# updown_counter.net
KiCad netlist of a schematic drawn in EAGLE
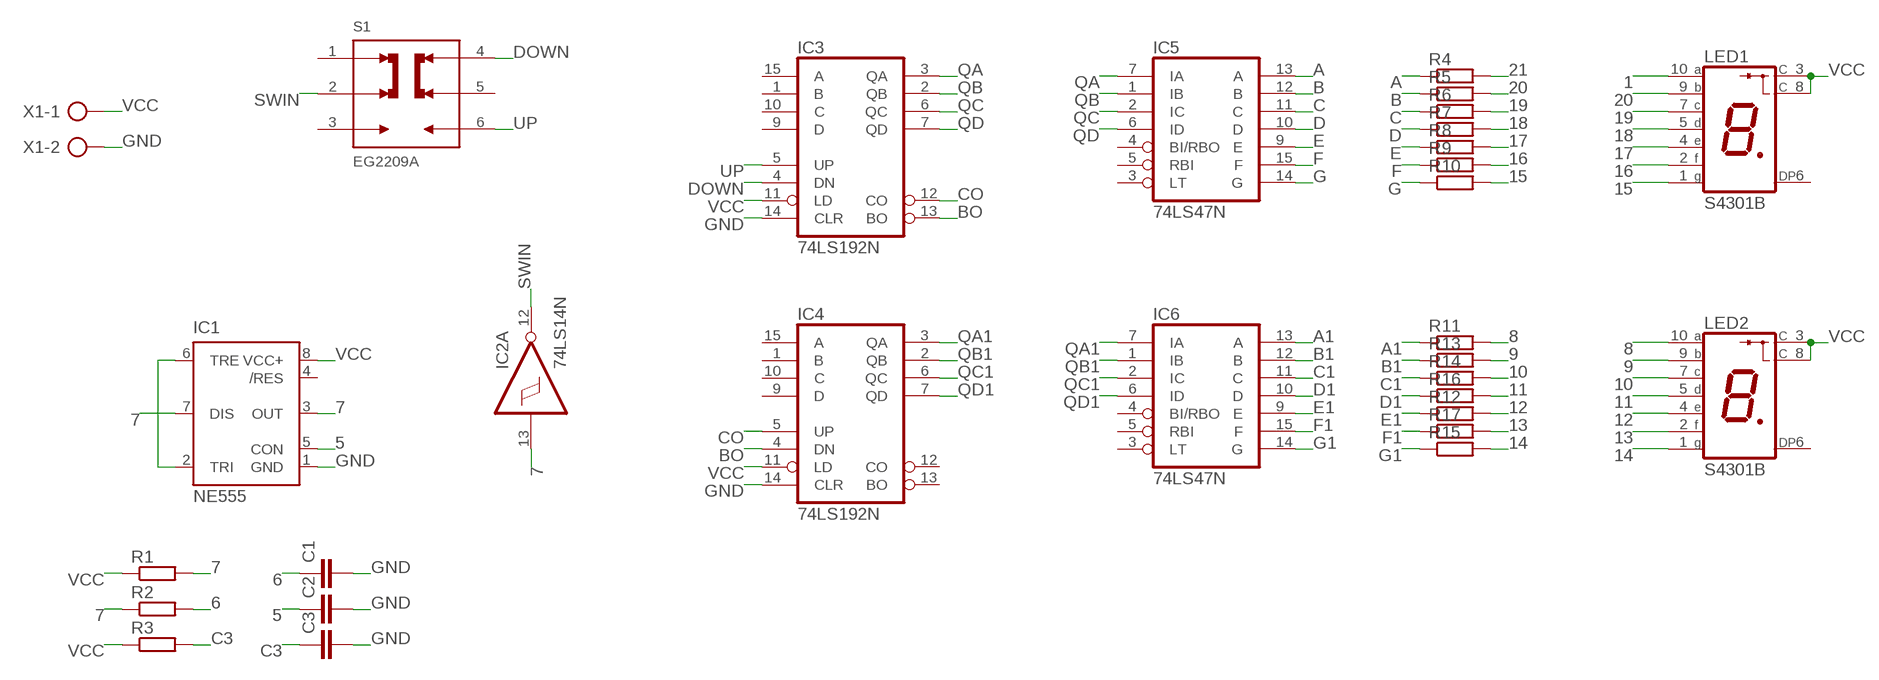
[diagram p0: schematic, sheet 1]

(export (version "E")
  (design (tool "Eeschema 10.0.6"))
  (components
    (comp (ref "C1")
      (value "C-EU025-025X050")
      (footprint "eagle-import:C025-025X050")
      (libsource (lib "eagle-import") (part "C-EU025-025X050"))
    )
    (comp (ref "C2")
      (value "C-EU025-025X050")
      (footprint "eagle-import:C025-025X050")
      (libsource (lib "eagle-import") (part "C-EU025-025X050"))
    )
    (comp (ref "C3")
      (value "C-EU025-025X050")
      (footprint "eagle-import:C025-025X050")
      (libsource (lib "eagle-import") (part "C-EU025-025X050"))
    )
    (comp (ref "IC1")
      (value "NE555")
      (footprint "eagle-import:DIL-08")
      (fields (field (name "MF") "Arrow Electronics") (field (name "MPN") "NE555N"))
      (libsource (lib "eagle-import") (part "NE555"))
    )
    (comp (ref "IC2")
      (value "74LS14N")
      (footprint "eagle-import:DIL14")
      (libsource (lib "eagle-import") (part "7414NLS"))
    )
    (comp (ref "IC3")
      (value "74LS192N")
      (footprint "eagle-import:DIL16")
      (libsource (lib "eagle-import") (part "74192NLS"))
    )
    (comp (ref "IC4")
      (value "74LS192N")
      (footprint "eagle-import:DIL16")
      (libsource (lib "eagle-import") (part "74192NLS"))
    )
    (comp (ref "IC5")
      (value "74LS47N")
      (footprint "eagle-import:DIL16")
      (libsource (lib "eagle-import") (part "7447NLS"))
    )
    (comp (ref "IC6")
      (value "74LS47N")
      (footprint "eagle-import:DIL16")
      (libsource (lib "eagle-import") (part "7447NLS"))
    )
    (comp (ref "LED1")
      (value "S4301B")
      (footprint "eagle-import:S4301B")
      (libsource (lib "eagle-import") (part "S4301B"))
    )
    (comp (ref "LED2")
      (value "S4301B")
      (footprint "eagle-import:S4301B")
      (libsource (lib "eagle-import") (part "S4301B"))
    )
    (comp (ref "R1")
      (value "R-EU_0207/10")
      (footprint "eagle-import:0207_10")
      (libsource (lib "eagle-import") (part "R-EU_0207/10"))
    )
    (comp (ref "R2")
      (value "R-EU_0207/10")
      (footprint "eagle-import:0207_10")
      (libsource (lib "eagle-import") (part "R-EU_0207/10"))
    )
    (comp (ref "R3")
      (value "R-EU_0207/10")
      (footprint "eagle-import:0207_10")
      (libsource (lib "eagle-import") (part "R-EU_0207/10"))
    )
    (comp (ref "R4")
      (value "R-EU_0207/10")
      (footprint "eagle-import:0207_10")
      (libsource (lib "eagle-import") (part "R-EU_0207/10"))
    )
    (comp (ref "R5")
      (value "R-EU_0207/10")
      (footprint "eagle-import:0207_10")
      (libsource (lib "eagle-import") (part "R-EU_0207/10"))
    )
    (comp (ref "R6")
      (value "R-EU_0207/10")
      (footprint "eagle-import:0207_10")
      (libsource (lib "eagle-import") (part "R-EU_0207/10"))
    )
    (comp (ref "R7")
      (value "R-EU_0207/10")
      (footprint "eagle-import:0207_10")
      (libsource (lib "eagle-import") (part "R-EU_0207/10"))
    )
    (comp (ref "R8")
      (value "R-EU_0207/10")
      (footprint "eagle-import:0207_10")
      (libsource (lib "eagle-import") (part "R-EU_0207/10"))
    )
    (comp (ref "R9")
      (value "R-EU_0207/10")
      (footprint "eagle-import:0207_10")
      (libsource (lib "eagle-import") (part "R-EU_0207/10"))
    )
    (comp (ref "R10")
      (value "R-EU_0207/10")
      (footprint "eagle-import:0207_10")
      (libsource (lib "eagle-import") (part "R-EU_0207/10"))
    )
    (comp (ref "R11")
      (value "R-EU_0207/10")
      (footprint "eagle-import:0207_10")
      (libsource (lib "eagle-import") (part "R-EU_0207/10"))
    )
    (comp (ref "R12")
      (value "R-EU_0207/10")
      (footprint "eagle-import:0207_10")
      (libsource (lib "eagle-import") (part "R-EU_0207/10"))
    )
    (comp (ref "R13")
      (value "R-EU_0207/10")
      (footprint "eagle-import:0207_10")
      (libsource (lib "eagle-import") (part "R-EU_0207/10"))
    )
    (comp (ref "R14")
      (value "R-EU_0207/10")
      (footprint "eagle-import:0207_10")
      (libsource (lib "eagle-import") (part "R-EU_0207/10"))
    )
    (comp (ref "R15")
      (value "R-EU_0207/10")
      (footprint "eagle-import:0207_10")
      (libsource (lib "eagle-import") (part "R-EU_0207/10"))
    )
    (comp (ref "R16")
      (value "R-EU_0207/10")
      (footprint "eagle-import:0207_10")
      (libsource (lib "eagle-import") (part "R-EU_0207/10"))
    )
    (comp (ref "R17")
      (value "R-EU_0207/10")
      (footprint "eagle-import:0207_10")
      (libsource (lib "eagle-import") (part "R-EU_0207/10"))
    )
    (comp (ref "S1")
      (value "EG2209A")
      (footprint "eagle-import:SW_EG2209A")
      (fields (field (name "MF") "E-Switch"))
      (libsource (lib "eagle-import") (part "EG2209A"))
    )
    (comp (ref "X1")
      (value "AK300/2")
      (footprint "eagle-import:AK300_2")
      (libsource (lib "eagle-import") (part "AK300/2"))
    )
  )
  (nets
    (net (code "1") (name "/1") (class "Default")
      (node (ref "LED1") (pin "10") (pinfunction "A_10") (pintype "passive"))
    )
    (net (code "2") (name "/5") (class "Default")
      (node (ref "C2") (pin "1") (pinfunction "1_1") (pintype "passive"))
      (node (ref "IC1") (pin "5") (pinfunction "CON_5") (pintype "input"))
    )
    (net (code "3") (name "/6") (class "Default")
      (node (ref "C1") (pin "1") (pinfunction "1_1") (pintype "passive"))
      (node (ref "R2") (pin "2") (pinfunction "2_2") (pintype "passive"))
    )
    (net (code "4") (name "/7") (class "Default")
      (node (ref "IC1") (pin "3") (pinfunction "OUT_3") (pintype "output"))
      (node (ref "IC1") (pin "7") (pinfunction "DIS_7") (pintype "input"))
      (node (ref "IC2") (pin "13") (pinfunction "I_13") (pintype "input"))
      (node (ref "R1") (pin "2") (pinfunction "2_2") (pintype "passive"))
      (node (ref "R2") (pin "1") (pinfunction "1_1") (pintype "passive"))
    )
    (net (code "5") (name "/8") (class "Default")
      (node (ref "LED2") (pin "10") (pinfunction "A_10") (pintype "passive"))
      (node (ref "R11") (pin "2") (pinfunction "2_2") (pintype "passive"))
    )
    (net (code "6") (name "/9") (class "Default")
      (node (ref "LED2") (pin "9") (pinfunction "B_9") (pintype "passive"))
      (node (ref "R13") (pin "2") (pinfunction "2_2") (pintype "passive"))
    )
    (net (code "7") (name "/10") (class "Default")
      (node (ref "LED2") (pin "7") (pinfunction "C_7") (pintype "passive"))
      (node (ref "R14") (pin "2") (pinfunction "2_2") (pintype "passive"))
    )
    (net (code "8") (name "/11") (class "Default")
      (node (ref "LED2") (pin "5") (pinfunction "D_5") (pintype "passive"))
      (node (ref "R16") (pin "2") (pinfunction "2_2") (pintype "passive"))
    )
    (net (code "9") (name "/12") (class "Default")
      (node (ref "LED2") (pin "4") (pinfunction "E_4") (pintype "passive"))
      (node (ref "R12") (pin "2") (pinfunction "2_2") (pintype "passive"))
    )
    (net (code "10") (name "/13") (class "Default")
      (node (ref "LED2") (pin "2") (pinfunction "F_2") (pintype "passive"))
      (node (ref "R17") (pin "2") (pinfunction "2_2") (pintype "passive"))
    )
    (net (code "11") (name "/14") (class "Default")
      (node (ref "LED2") (pin "1") (pinfunction "G_1") (pintype "passive"))
      (node (ref "R15") (pin "2") (pinfunction "2_2") (pintype "passive"))
    )
    (net (code "12") (name "/15") (class "Default")
      (node (ref "LED1") (pin "1") (pinfunction "G_1") (pintype "passive"))
      (node (ref "R10") (pin "2") (pinfunction "2_2") (pintype "passive"))
    )
    (net (code "13") (name "/16") (class "Default")
      (node (ref "LED1") (pin "2") (pinfunction "F_2") (pintype "passive"))
      (node (ref "R9") (pin "2") (pinfunction "2_2") (pintype "passive"))
    )
    (net (code "14") (name "/17") (class "Default")
      (node (ref "LED1") (pin "4") (pinfunction "E_4") (pintype "passive"))
      (node (ref "R8") (pin "2") (pinfunction "2_2") (pintype "passive"))
    )
    (net (code "15") (name "/18") (class "Default")
      (node (ref "LED1") (pin "5") (pinfunction "D_5") (pintype "passive"))
      (node (ref "R7") (pin "2") (pinfunction "2_2") (pintype "passive"))
    )
    (net (code "16") (name "/19") (class "Default")
      (node (ref "LED1") (pin "7") (pinfunction "C_7") (pintype "passive"))
      (node (ref "R6") (pin "2") (pinfunction "2_2") (pintype "passive"))
    )
    (net (code "17") (name "/20") (class "Default")
      (node (ref "LED1") (pin "9") (pinfunction "B_9") (pintype "passive"))
      (node (ref "R5") (pin "2") (pinfunction "2_2") (pintype "passive"))
    )
    (net (code "18") (name "/21") (class "Default")
      (node (ref "R4") (pin "2") (pinfunction "2_2") (pintype "passive"))
    )
    (net (code "19") (name "/A") (class "Default")
      (node (ref "IC5") (pin "13") (pinfunction "A_13") (pintype "output"))
      (node (ref "R4") (pin "1") (pinfunction "1_1") (pintype "passive"))
    )
    (net (code "20") (name "/A1") (class "Default")
      (node (ref "IC6") (pin "13") (pinfunction "A_13") (pintype "output"))
      (node (ref "R11") (pin "1") (pinfunction "1_1") (pintype "passive"))
    )
    (net (code "21") (name "/B") (class "Default")
      (node (ref "IC5") (pin "12") (pinfunction "B_12") (pintype "output"))
      (node (ref "R5") (pin "1") (pinfunction "1_1") (pintype "passive"))
    )
    (net (code "22") (name "/B1") (class "Default")
      (node (ref "IC6") (pin "12") (pinfunction "B_12") (pintype "output"))
      (node (ref "R13") (pin "1") (pinfunction "1_1") (pintype "passive"))
    )
    (net (code "23") (name "/BO") (class "Default")
      (node (ref "IC3") (pin "13") (pinfunction "BO_13") (pintype "output"))
      (node (ref "IC4") (pin "4") (pinfunction "DN_4") (pintype "input"))
    )
    (net (code "24") (name "/C") (class "Default")
      (node (ref "IC5") (pin "11") (pinfunction "C_11") (pintype "output"))
      (node (ref "R6") (pin "1") (pinfunction "1_1") (pintype "passive"))
    )
    (net (code "25") (name "/C1") (class "Default")
      (node (ref "IC6") (pin "11") (pinfunction "C_11") (pintype "output"))
      (node (ref "R14") (pin "1") (pinfunction "1_1") (pintype "passive"))
    )
    (net (code "26") (name "/C3") (class "Default")
      (node (ref "C3") (pin "1") (pinfunction "1_1") (pintype "passive"))
      (node (ref "R3") (pin "2") (pinfunction "2_2") (pintype "passive"))
    )
    (net (code "27") (name "/CO") (class "Default")
      (node (ref "IC3") (pin "12") (pinfunction "CO_12") (pintype "output"))
      (node (ref "IC4") (pin "5") (pinfunction "UP_5") (pintype "input"))
    )
    (net (code "28") (name "/D") (class "Default")
      (node (ref "IC5") (pin "10") (pinfunction "D_10") (pintype "output"))
      (node (ref "R7") (pin "1") (pinfunction "1_1") (pintype "passive"))
    )
    (net (code "29") (name "/D1") (class "Default")
      (node (ref "IC6") (pin "10") (pinfunction "D_10") (pintype "output"))
      (node (ref "R16") (pin "1") (pinfunction "1_1") (pintype "passive"))
    )
    (net (code "30") (name "/DOWN") (class "Default")
      (node (ref "IC3") (pin "4") (pinfunction "DN_4") (pintype "input"))
      (node (ref "S1") (pin "4") (pinfunction "4_4") (pintype "passive"))
    )
    (net (code "31") (name "/E") (class "Default")
      (node (ref "IC5") (pin "9") (pinfunction "E_9") (pintype "output"))
      (node (ref "R8") (pin "1") (pinfunction "1_1") (pintype "passive"))
    )
    (net (code "32") (name "/E1") (class "Default")
      (node (ref "IC6") (pin "9") (pinfunction "E_9") (pintype "output"))
      (node (ref "R12") (pin "1") (pinfunction "1_1") (pintype "passive"))
    )
    (net (code "33") (name "/F") (class "Default")
      (node (ref "IC5") (pin "15") (pinfunction "F_15") (pintype "output"))
      (node (ref "R9") (pin "1") (pinfunction "1_1") (pintype "passive"))
    )
    (net (code "34") (name "/F1") (class "Default")
      (node (ref "IC6") (pin "15") (pinfunction "F_15") (pintype "output"))
      (node (ref "R17") (pin "1") (pinfunction "1_1") (pintype "passive"))
    )
    (net (code "35") (name "/G") (class "Default")
      (node (ref "IC5") (pin "14") (pinfunction "G_14") (pintype "output"))
      (node (ref "R10") (pin "1") (pinfunction "1_1") (pintype "passive"))
    )
    (net (code "36") (name "/G1") (class "Default")
      (node (ref "IC6") (pin "14") (pinfunction "G_14") (pintype "output"))
      (node (ref "R15") (pin "1") (pinfunction "1_1") (pintype "passive"))
    )
    (net (code "37") (name "/GND") (class "Default")
      (node (ref "C1") (pin "2") (pinfunction "2_2") (pintype "passive"))
      (node (ref "C2") (pin "2") (pinfunction "2_2") (pintype "passive"))
      (node (ref "C3") (pin "2") (pinfunction "2_2") (pintype "passive"))
      (node (ref "IC1") (pin "1") (pinfunction "GND_1") (pintype "power_in"))
      (node (ref "IC3") (pin "14") (pinfunction "CLR_14") (pintype "input"))
      (node (ref "IC4") (pin "14") (pinfunction "CLR_14") (pintype "input"))
      (node (ref "X1") (pin "2") (pinfunction "KL_2") (pintype "passive"))
    )
    (net (code "38") (name "/QA") (class "Default")
      (node (ref "IC3") (pin "3") (pinfunction "QA_3") (pintype "output"))
      (node (ref "IC5") (pin "7") (pinfunction "IA_7") (pintype "input"))
    )
    (net (code "39") (name "/QA1") (class "Default")
      (node (ref "IC4") (pin "3") (pinfunction "QA_3") (pintype "output"))
      (node (ref "IC6") (pin "7") (pinfunction "IA_7") (pintype "input"))
    )
    (net (code "40") (name "/QB") (class "Default")
      (node (ref "IC3") (pin "2") (pinfunction "QB_2") (pintype "output"))
      (node (ref "IC5") (pin "1") (pinfunction "IB_1") (pintype "input"))
    )
    (net (code "41") (name "/QB1") (class "Default")
      (node (ref "IC4") (pin "2") (pinfunction "QB_2") (pintype "output"))
      (node (ref "IC6") (pin "1") (pinfunction "IB_1") (pintype "input"))
    )
    (net (code "42") (name "/QC") (class "Default")
      (node (ref "IC3") (pin "6") (pinfunction "QC_6") (pintype "output"))
      (node (ref "IC5") (pin "2") (pinfunction "IC_2") (pintype "input"))
    )
    (net (code "43") (name "/QC1") (class "Default")
      (node (ref "IC4") (pin "6") (pinfunction "QC_6") (pintype "output"))
      (node (ref "IC6") (pin "2") (pinfunction "IC_2") (pintype "input"))
    )
    (net (code "44") (name "/QD") (class "Default")
      (node (ref "IC3") (pin "7") (pinfunction "QD_7") (pintype "output"))
      (node (ref "IC5") (pin "6") (pinfunction "ID_6") (pintype "input"))
    )
    (net (code "45") (name "/QD1") (class "Default")
      (node (ref "IC4") (pin "7") (pinfunction "QD_7") (pintype "output"))
      (node (ref "IC6") (pin "6") (pinfunction "ID_6") (pintype "input"))
    )
    (net (code "46") (name "/SWIN") (class "Default")
      (node (ref "IC2") (pin "12") (pinfunction "O_12") (pintype "output"))
      (node (ref "S1") (pin "2") (pinfunction "2_2") (pintype "passive"))
    )
    (net (code "47") (name "/UP") (class "Default")
      (node (ref "IC3") (pin "5") (pinfunction "UP_5") (pintype "input"))
      (node (ref "S1") (pin "6") (pinfunction "6_6") (pintype "passive"))
    )
    (net (code "48") (name "/VCC") (class "Default")
      (node (ref "IC1") (pin "8") (pinfunction "VCC+_8") (pintype "power_in"))
      (node (ref "IC3") (pin "11") (pinfunction "LD_11") (pintype "input"))
      (node (ref "IC4") (pin "11") (pinfunction "LD_11") (pintype "input"))
      (node (ref "LED1") (pin "3") (pinfunction "C_3") (pintype "passive"))
      (node (ref "LED1") (pin "8") (pinfunction "C_8") (pintype "passive"))
      (node (ref "LED2") (pin "3") (pinfunction "C_3") (pintype "passive"))
      (node (ref "LED2") (pin "8") (pinfunction "C_8") (pintype "passive"))
      (node (ref "R1") (pin "1") (pinfunction "1_1") (pintype "passive"))
      (node (ref "R3") (pin "1") (pinfunction "1_1") (pintype "passive"))
      (node (ref "X1") (pin "1") (pinfunction "KL_1") (pintype "passive"))
    )
    (net (code "49") (name "Net-(IC1-TRE)") (class "Default")
      (node (ref "IC1") (pin "2") (pinfunction "TRI_2") (pintype "input"))
      (node (ref "IC1") (pin "6") (pinfunction "TRE_6") (pintype "input"))
    )
    (net (code "50") (name "unconnected-(IC1-{slash}RES-Pad4)") (class "Default")
      (node (ref "IC1") (pin "4") (pinfunction "/RES_4") (pintype "input"))
    )
    (net (code "51") (name "unconnected-(IC3A-A-Pad15)") (class "Default")
      (node (ref "IC3") (pin "15") (pinfunction "A_15") (pintype "input"))
    )
    (net (code "52") (name "unconnected-(IC3A-B-Pad1)") (class "Default")
      (node (ref "IC3") (pin "1") (pinfunction "B_1") (pintype "input"))
    )
    (net (code "53") (name "unconnected-(IC3A-C-Pad10)") (class "Default")
      (node (ref "IC3") (pin "10") (pinfunction "C_10") (pintype "input"))
    )
    (net (code "54") (name "unconnected-(IC3A-D-Pad9)") (class "Default")
      (node (ref "IC3") (pin "9") (pinfunction "D_9") (pintype "input"))
    )
    (net (code "55") (name "unconnected-(IC4A-A-Pad15)") (class "Default")
      (node (ref "IC4") (pin "15") (pinfunction "A_15") (pintype "input"))
    )
    (net (code "56") (name "unconnected-(IC4A-B-Pad1)") (class "Default")
      (node (ref "IC4") (pin "1") (pinfunction "B_1") (pintype "input"))
    )
    (net (code "57") (name "unconnected-(IC4A-BO-Pad13)") (class "Default")
      (node (ref "IC4") (pin "13") (pinfunction "BO_13") (pintype "output"))
    )
    (net (code "58") (name "unconnected-(IC4A-C-Pad10)") (class "Default")
      (node (ref "IC4") (pin "10") (pinfunction "C_10") (pintype "input"))
    )
    (net (code "59") (name "unconnected-(IC4A-CO-Pad12)") (class "Default")
      (node (ref "IC4") (pin "12") (pinfunction "CO_12") (pintype "output"))
    )
    (net (code "60") (name "unconnected-(IC4A-D-Pad9)") (class "Default")
      (node (ref "IC4") (pin "9") (pinfunction "D_9") (pintype "input"))
    )
    (net (code "61") (name "unconnected-(IC5A-BI{slash}RBO-Pad4)") (class "Default")
      (node (ref "IC5") (pin "4") (pinfunction "BI/RBO_4") (pintype "input"))
    )
    (net (code "62") (name "unconnected-(IC5A-LT-Pad3)") (class "Default")
      (node (ref "IC5") (pin "3") (pinfunction "LT_3") (pintype "input"))
    )
    (net (code "63") (name "unconnected-(IC5A-RBI-Pad5)") (class "Default")
      (node (ref "IC5") (pin "5") (pinfunction "RBI_5") (pintype "input"))
    )
    (net (code "64") (name "unconnected-(IC6A-BI{slash}RBO-Pad4)") (class "Default")
      (node (ref "IC6") (pin "4") (pinfunction "BI/RBO_4") (pintype "input"))
    )
    (net (code "65") (name "unconnected-(IC6A-LT-Pad3)") (class "Default")
      (node (ref "IC6") (pin "3") (pinfunction "LT_3") (pintype "input"))
    )
    (net (code "66") (name "unconnected-(IC6A-RBI-Pad5)") (class "Default")
      (node (ref "IC6") (pin "5") (pinfunction "RBI_5") (pintype "input"))
    )
    (net (code "67") (name "unconnected-(LED1-DP-Pad6)") (class "Default")
      (node (ref "LED1") (pin "6") (pinfunction "DP_6") (pintype "passive"))
    )
    (net (code "68") (name "unconnected-(LED2-DP-Pad6)") (class "Default")
      (node (ref "LED2") (pin "6") (pinfunction "DP_6") (pintype "passive"))
    )
    (net (code "69") (name "unconnected-(S1-Pad1)") (class "Default")
      (node (ref "S1") (pin "1") (pinfunction "1_1") (pintype "passive"))
    )
    (net (code "70") (name "unconnected-(S1-Pad3)") (class "Default")
      (node (ref "S1") (pin "3") (pinfunction "3_3") (pintype "passive"))
    )
    (net (code "71") (name "unconnected-(S1-Pad5)") (class "Default")
      (node (ref "S1") (pin "5") (pinfunction "5_5") (pintype "passive"))
    )
  )
)
